# EMILL_V2.net
KiCad netlist of a schematic drawn in EAGLE
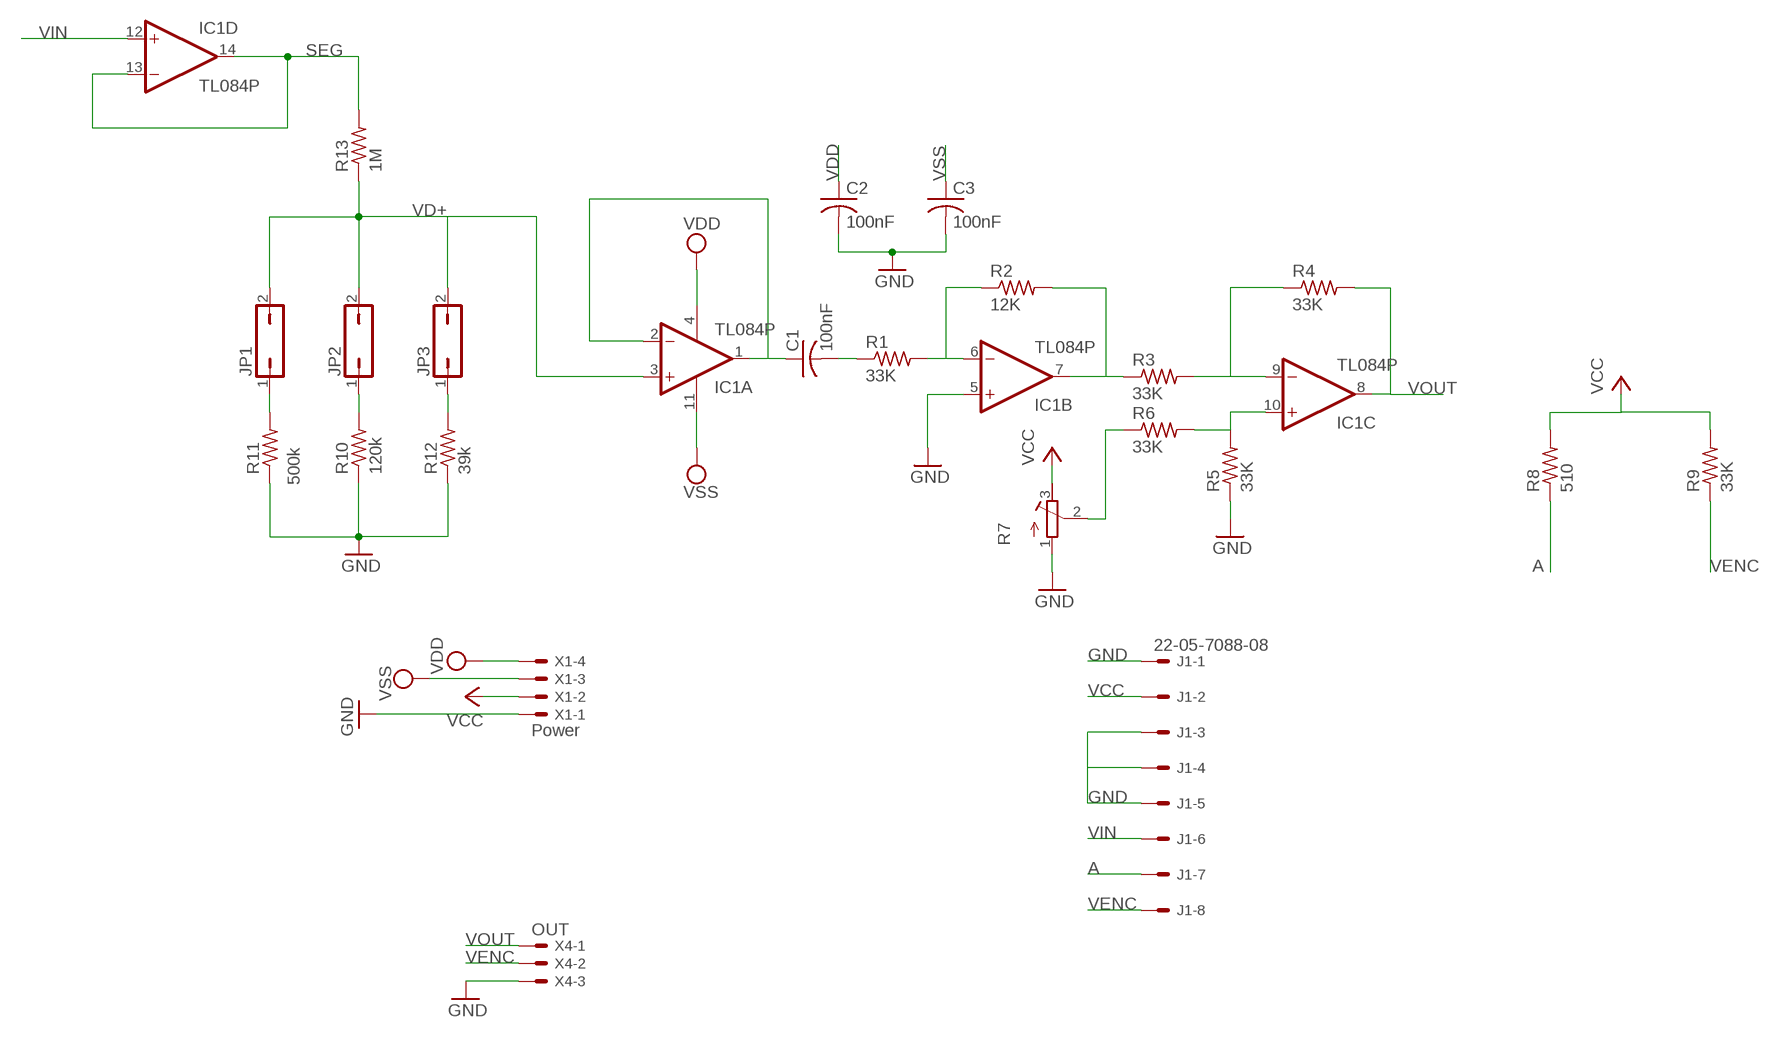
[diagram p0: schematic, sheet 1]

(export (version "E")
  (design (tool "Eeschema 10.0.6"))
  (components
    (comp (ref "C1")
      (value "100nF")
      (footprint "eagle-import:C025-025X050")
      (libsource (lib "eagle-import") (part "C-US025-025X050"))
    )
    (comp (ref "C2")
      (value "100nF")
      (footprint "eagle-import:C025-025X050")
      (libsource (lib "eagle-import") (part "C-US025-025X050"))
    )
    (comp (ref "C3")
      (value "100nF")
      (footprint "eagle-import:C025-025X050")
      (libsource (lib "eagle-import") (part "C-US025-025X050"))
    )
    (comp (ref "IC1")
      (value "TL084P")
      (footprint "eagle-import:DIL14")
      (libsource (lib "eagle-import") (part "TL084P"))
    )
    (comp (ref "J1")
      (value "22-05-7088-08")
      (footprint "eagle-import:7395-08")
      (fields (field (name "MF") "MOLEX"))
      (libsource (lib "eagle-import") (part "22-?-0805-7088"))
    )
    (comp (ref "JP1")
      (value "JP1Q")
      (footprint "eagle-import:JP1")
      (libsource (lib "eagle-import") (part "JP1Q"))
    )
    (comp (ref "JP2")
      (value "JP1Q")
      (footprint "eagle-import:JP1")
      (libsource (lib "eagle-import") (part "JP1Q"))
    )
    (comp (ref "JP3")
      (value "JP1Q")
      (footprint "eagle-import:JP1")
      (libsource (lib "eagle-import") (part "JP1Q"))
    )
    (comp (ref "R1")
      (value "33K")
      (footprint "eagle-import:0207_10")
      (libsource (lib "eagle-import") (part "R-US_0207/10"))
    )
    (comp (ref "R2")
      (value "12K")
      (footprint "eagle-import:0207_10")
      (libsource (lib "eagle-import") (part "R-US_0207/10"))
    )
    (comp (ref "R3")
      (value "33K")
      (footprint "eagle-import:0207_10")
      (libsource (lib "eagle-import") (part "R-US_0207/10"))
    )
    (comp (ref "R4")
      (value "33K")
      (footprint "eagle-import:0207_10")
      (libsource (lib "eagle-import") (part "R-US_0207/10"))
    )
    (comp (ref "R5")
      (value "33K")
      (footprint "eagle-import:0207_10")
      (libsource (lib "eagle-import") (part "R-US_0207/10"))
    )
    (comp (ref "R6")
      (value "33K")
      (footprint "eagle-import:0207_10")
      (libsource (lib "eagle-import") (part "R-US_0207/10"))
    )
    (comp (ref "R7")
      (value "R-TRIMM64W")
      (footprint "eagle-import:RTRIM64W")
      (libsource (lib "eagle-import") (part "R-TRIMM64W"))
    )
    (comp (ref "R8")
      (value "510")
      (footprint "eagle-import:0207_10")
      (libsource (lib "eagle-import") (part "R-US_0207/10"))
    )
    (comp (ref "R9")
      (value "33K")
      (footprint "eagle-import:0207_10")
      (libsource (lib "eagle-import") (part "R-US_0207/10"))
    )
    (comp (ref "R10")
      (value "120k")
      (footprint "eagle-import:0207_10")
      (libsource (lib "eagle-import") (part "R-US_0207/10"))
    )
    (comp (ref "R11")
      (value "500k")
      (footprint "eagle-import:0207_10")
      (libsource (lib "eagle-import") (part "R-US_0207/10"))
    )
    (comp (ref "R12")
      (value "39k")
      (footprint "eagle-import:0207_10")
      (libsource (lib "eagle-import") (part "R-US_0207/10"))
    )
    (comp (ref "R13")
      (value "1M")
      (footprint "eagle-import:0207_10")
      (libsource (lib "eagle-import") (part "R-US_0207/10"))
    )
    (comp (ref "X1")
      (value "Power")
      (footprint "eagle-import:22-23-2041")
      (fields (field (name "MF") "MOLEX") (field (name "MPN") "22-23-2041"))
      (libsource (lib "eagle-import") (part "22-23-2041"))
    )
    (comp (ref "X4")
      (value "OUT")
      (footprint "eagle-import:22-23-2031")
      (fields (field (name "MF") "MOLEX") (field (name "MPN") "22-23-2031"))
      (libsource (lib "eagle-import") (part "22-23-2031"))
    )
  )
  (nets
    (net (code "1") (name "/A") (class "Default")
      (node (ref "J1") (pin "7") (pinfunction "S_7") (pintype "passive"))
      (node (ref "R8") (pin "1") (pinfunction "1_1") (pintype "passive"))
    )
    (net (code "2") (name "/SEG") (class "Default")
      (node (ref "IC1") (pin "13") (pinfunction "-IN_13") (pintype "input"))
      (node (ref "IC1") (pin "14") (pinfunction "OUT_14") (pintype "output"))
      (node (ref "R13") (pin "2") (pinfunction "2_2") (pintype "passive"))
    )
    (net (code "3") (name "/VD+") (class "Default")
      (node (ref "IC1") (pin "3") (pinfunction "+IN_3") (pintype "input"))
      (node (ref "JP1") (pin "2") (pinfunction "2_2") (pintype "passive"))
      (node (ref "JP2") (pin "2") (pinfunction "2_2") (pintype "passive"))
      (node (ref "JP3") (pin "2") (pinfunction "2_2") (pintype "passive"))
      (node (ref "R13") (pin "1") (pinfunction "1_1") (pintype "passive"))
    )
    (net (code "4") (name "/VENC") (class "Default")
      (node (ref "J1") (pin "8") (pinfunction "S_8") (pintype "passive"))
      (node (ref "R9") (pin "1") (pinfunction "1_1") (pintype "passive"))
      (node (ref "X4") (pin "2") (pinfunction "S_2") (pintype "passive"))
    )
    (net (code "5") (name "/VIN") (class "Default")
      (node (ref "IC1") (pin "12") (pinfunction "+IN_12") (pintype "input"))
      (node (ref "J1") (pin "6") (pinfunction "S_6") (pintype "passive"))
    )
    (net (code "6") (name "/VOUT") (class "Default")
      (node (ref "IC1") (pin "8") (pinfunction "OUT_8") (pintype "output"))
      (node (ref "R4") (pin "2") (pinfunction "2_2") (pintype "passive"))
      (node (ref "X4") (pin "1") (pinfunction "S_1") (pintype "passive"))
    )
    (net (code "7") (name "GND") (class "Default")
      (node (ref "C2") (pin "2") (pinfunction "2_2") (pintype "passive"))
      (node (ref "C3") (pin "2") (pinfunction "2_2") (pintype "passive"))
      (node (ref "IC1") (pin "5") (pinfunction "+IN_5") (pintype "input"))
      (node (ref "J1") (pin "1") (pinfunction "S_1") (pintype "passive"))
      (node (ref "J1") (pin "3") (pinfunction "S_3") (pintype "passive"))
      (node (ref "J1") (pin "4") (pinfunction "S_4") (pintype "passive"))
      (node (ref "J1") (pin "5") (pinfunction "S_5") (pintype "passive"))
      (node (ref "R10") (pin "1") (pinfunction "1_1") (pintype "passive"))
      (node (ref "R11") (pin "1") (pinfunction "1_1") (pintype "passive"))
      (node (ref "R12") (pin "1") (pinfunction "1_1") (pintype "passive"))
      (node (ref "R5") (pin "1") (pinfunction "1_1") (pintype "passive"))
      (node (ref "R7") (pin "1") (pinfunction "A_1") (pintype "passive"))
      (node (ref "X1") (pin "1") (pinfunction "S_1") (pintype "passive"))
      (node (ref "X4") (pin "3") (pinfunction "S_3") (pintype "passive"))
    )
    (net (code "8") (name "Net-(C1-Pad2)") (class "Default")
      (node (ref "C1") (pin "2") (pinfunction "2_2") (pintype "passive"))
      (node (ref "R1") (pin "1") (pinfunction "1_1") (pintype "passive"))
    )
    (net (code "9") (name "Net-(IC1A--IN)") (class "Default")
      (node (ref "C1") (pin "1") (pinfunction "1_1") (pintype "passive"))
      (node (ref "IC1") (pin "1") (pinfunction "OUT_1") (pintype "output"))
      (node (ref "IC1") (pin "2") (pinfunction "-IN_2") (pintype "input"))
    )
    (net (code "10") (name "Net-(IC1B--IN)") (class "Default")
      (node (ref "IC1") (pin "6") (pinfunction "-IN_6") (pintype "input"))
      (node (ref "R1") (pin "2") (pinfunction "2_2") (pintype "passive"))
      (node (ref "R2") (pin "1") (pinfunction "1_1") (pintype "passive"))
    )
    (net (code "11") (name "Net-(IC1B-OUT)") (class "Default")
      (node (ref "IC1") (pin "7") (pinfunction "OUT_7") (pintype "output"))
      (node (ref "R2") (pin "2") (pinfunction "2_2") (pintype "passive"))
      (node (ref "R3") (pin "1") (pinfunction "1_1") (pintype "passive"))
    )
    (net (code "12") (name "Net-(IC1C-+IN)") (class "Default")
      (node (ref "IC1") (pin "10") (pinfunction "+IN_10") (pintype "input"))
      (node (ref "R5") (pin "2") (pinfunction "2_2") (pintype "passive"))
      (node (ref "R6") (pin "2") (pinfunction "2_2") (pintype "passive"))
    )
    (net (code "13") (name "Net-(IC1C--IN)") (class "Default")
      (node (ref "IC1") (pin "9") (pinfunction "-IN_9") (pintype "input"))
      (node (ref "R3") (pin "2") (pinfunction "2_2") (pintype "passive"))
      (node (ref "R4") (pin "1") (pinfunction "1_1") (pintype "passive"))
    )
    (net (code "14") (name "Net-(JP1-Pad1)") (class "Default")
      (node (ref "JP1") (pin "1") (pinfunction "1_1") (pintype "passive"))
      (node (ref "R11") (pin "2") (pinfunction "2_2") (pintype "passive"))
    )
    (net (code "15") (name "Net-(JP2-Pad1)") (class "Default")
      (node (ref "JP2") (pin "1") (pinfunction "1_1") (pintype "passive"))
      (node (ref "R10") (pin "2") (pinfunction "2_2") (pintype "passive"))
    )
    (net (code "16") (name "Net-(JP3-Pad1)") (class "Default")
      (node (ref "JP3") (pin "1") (pinfunction "1_1") (pintype "passive"))
      (node (ref "R12") (pin "2") (pinfunction "2_2") (pintype "passive"))
    )
    (net (code "17") (name "Net-(R7-S)") (class "Default")
      (node (ref "R6") (pin "1") (pinfunction "1_1") (pintype "passive"))
      (node (ref "R7") (pin "2") (pinfunction "S_2") (pintype "passive"))
    )
    (net (code "18") (name "VCC") (class "Default")
      (node (ref "J1") (pin "2") (pinfunction "S_2") (pintype "passive"))
      (node (ref "R7") (pin "3") (pinfunction "E_3") (pintype "passive"))
      (node (ref "R8") (pin "2") (pinfunction "2_2") (pintype "passive"))
      (node (ref "R9") (pin "2") (pinfunction "2_2") (pintype "passive"))
      (node (ref "X1") (pin "2") (pinfunction "S_2") (pintype "passive"))
    )
    (net (code "19") (name "VDD") (class "Default")
      (node (ref "C2") (pin "1") (pinfunction "1_1") (pintype "passive"))
      (node (ref "IC1") (pin "4") (pinfunction "V+_4") (pintype "power_in"))
      (node (ref "X1") (pin "4") (pinfunction "S_4") (pintype "passive"))
    )
    (net (code "20") (name "VSS") (class "Default")
      (node (ref "C3") (pin "1") (pinfunction "1_1") (pintype "passive"))
      (node (ref "IC1") (pin "11") (pinfunction "V-_11") (pintype "power_in"))
      (node (ref "X1") (pin "3") (pinfunction "S_3") (pintype "passive"))
    )
  )
)
